# Relay_Control.net
KiCad netlist of a schematic drawn in Altium Designer
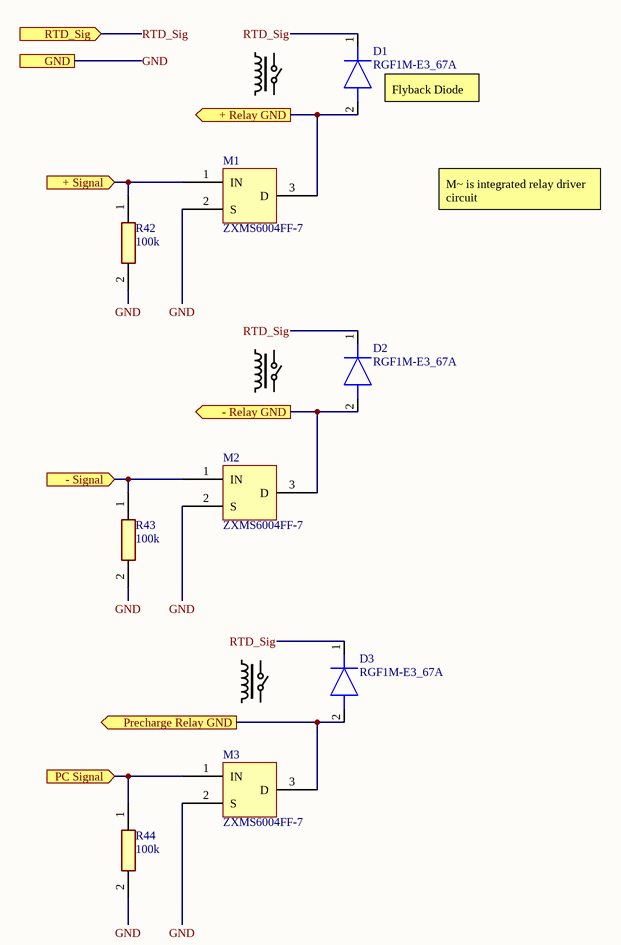
[diagram p0: Relay_Control.SchDoc]

(export (version "E")
  (design (tool "Eeschema 10.0.6"))
  (components
    (comp (ref "D1")
      (value "RGF1M-E3_67A")
      (footprint "SamacSys:DIOM5426X300N")
      (description "Diode")
      (fields
        (field (name "MANUFACTURER_PART_NUMBER") "RGF1M-E3/67A")
        (field (name "MOUSER PART NUMBER") "625-RGF1M-E3")
      )
      (libsource (lib "SamacSys") (part "RGF1M-E3_67A"))
    )
    (comp (ref "D2")
      (value "RGF1M-E3_67A")
      (footprint "SamacSys:DIOM5426X300N")
      (description "Diode")
      (fields
        (field (name "MANUFACTURER_PART_NUMBER") "RGF1M-E3/67A")
        (field (name "MOUSER PART NUMBER") "625-RGF1M-E3")
      )
      (libsource (lib "SamacSys") (part "RGF1M-E3_67A"))
    )
    (comp (ref "D3")
      (value "RGF1M-E3_67A")
      (footprint "SamacSys:DIOM5426X300N")
      (description "Diode")
      (fields
        (field (name "MANUFACTURER_PART_NUMBER") "RGF1M-E3/67A")
        (field (name "MOUSER PART NUMBER") "625-RGF1M-E3")
      )
      (libsource (lib "SamacSys") (part "RGF1M-E3_67A"))
    )
    (comp (ref "M1")
      (value "ZXMS6004FF-7")
      (footprint "SamacSys:SOT95P240X100-3N")
      (libsource (lib "SamacSys") (part "ZXMS6004FF-7"))
    )
    (comp (ref "M2")
      (value "ZXMS6004FF-7")
      (footprint "SamacSys:SOT95P240X100-3N")
      (libsource (lib "SamacSys") (part "ZXMS6004FF-7"))
    )
    (comp (ref "M3")
      (value "ZXMS6004FF-7")
      (footprint "SamacSys:SOT95P240X100-3N")
      (libsource (lib "SamacSys") (part "ZXMS6004FF-7"))
    )
    (comp (ref "R42")
      (value "100k")
      (footprint "SamacSys:RESC1608X55N")
      (description "Resistor")
      (fields
        (field (name "MANUFACTURER_PART_NUMBER") "CR0603-JW-104ELF")
        (field (name "MOUSER PART NUMBER") "652-CR0603-JW-104ELF")
      )
      (libsource (lib "*") (part "CR0603-JW-104ELF"))
    )
    (comp (ref "R43")
      (value "100k")
      (footprint "SamacSys:RESC1608X55N")
      (description "Resistor")
      (fields
        (field (name "MANUFACTURER_PART_NUMBER") "CR0603-JW-104ELF")
        (field (name "MOUSER PART NUMBER") "652-CR0603-JW-104ELF")
      )
      (libsource (lib "*") (part "CR0603-JW-104ELF"))
    )
    (comp (ref "R44")
      (value "100k")
      (footprint "SamacSys:RESC1608X55N")
      (description "Resistor")
      (fields
        (field (name "MANUFACTURER_PART_NUMBER") "CR0603-JW-104ELF")
        (field (name "MOUSER PART NUMBER") "652-CR0603-JW-104ELF")
      )
      (libsource (lib "*") (part "CR0603-JW-104ELF"))
    )
  )
  (nets
    (net (code "1") (name "/+ Relay GND") (class "Default")
      (node (ref "D1") (pin "2") (pinfunction "A_2") (pintype "passive"))
      (node (ref "M1") (pin "3") (pinfunction "D_3") (pintype "passive"))
    )
    (net (code "2") (name "/+ Signal") (class "Default")
      (node (ref "M1") (pin "1") (pinfunction "IN_1") (pintype "passive"))
      (node (ref "R42") (pin "1") (pinfunction "1_1") (pintype "passive"))
    )
    (net (code "3") (name "/- Relay GND") (class "Default")
      (node (ref "D2") (pin "2") (pinfunction "A_2") (pintype "passive"))
      (node (ref "M2") (pin "3") (pinfunction "D_3") (pintype "passive"))
    )
    (net (code "4") (name "/- Signal") (class "Default")
      (node (ref "M2") (pin "1") (pinfunction "IN_1") (pintype "passive"))
      (node (ref "R43") (pin "1") (pinfunction "1_1") (pintype "passive"))
    )
    (net (code "5") (name "/GND") (class "Default")
      (node (ref "M1") (pin "2") (pinfunction "S_2") (pintype "passive"))
      (node (ref "M2") (pin "2") (pinfunction "S_2") (pintype "passive"))
      (node (ref "M3") (pin "2") (pinfunction "S_2") (pintype "passive"))
      (node (ref "R42") (pin "2") (pinfunction "2_2") (pintype "passive"))
      (node (ref "R43") (pin "2") (pinfunction "2_2") (pintype "passive"))
      (node (ref "R44") (pin "2") (pinfunction "2_2") (pintype "passive"))
    )
    (net (code "6") (name "/PC Signal") (class "Default")
      (node (ref "M3") (pin "1") (pinfunction "IN_1") (pintype "passive"))
      (node (ref "R44") (pin "1") (pinfunction "1_1") (pintype "passive"))
    )
    (net (code "7") (name "/Precharge Relay GND") (class "Default")
      (node (ref "D3") (pin "2") (pinfunction "A_2") (pintype "passive"))
      (node (ref "M3") (pin "3") (pinfunction "D_3") (pintype "passive"))
    )
    (net (code "8") (name "/RTD_Sig") (class "Default")
      (node (ref "D1") (pin "1") (pinfunction "K_1") (pintype "passive"))
      (node (ref "D2") (pin "1") (pinfunction "K_1") (pintype "passive"))
      (node (ref "D3") (pin "1") (pinfunction "K_1") (pintype "passive"))
    )
  )
)
